# Extandboard.net
KiCad netlist of a schematic drawn in Altium Designer
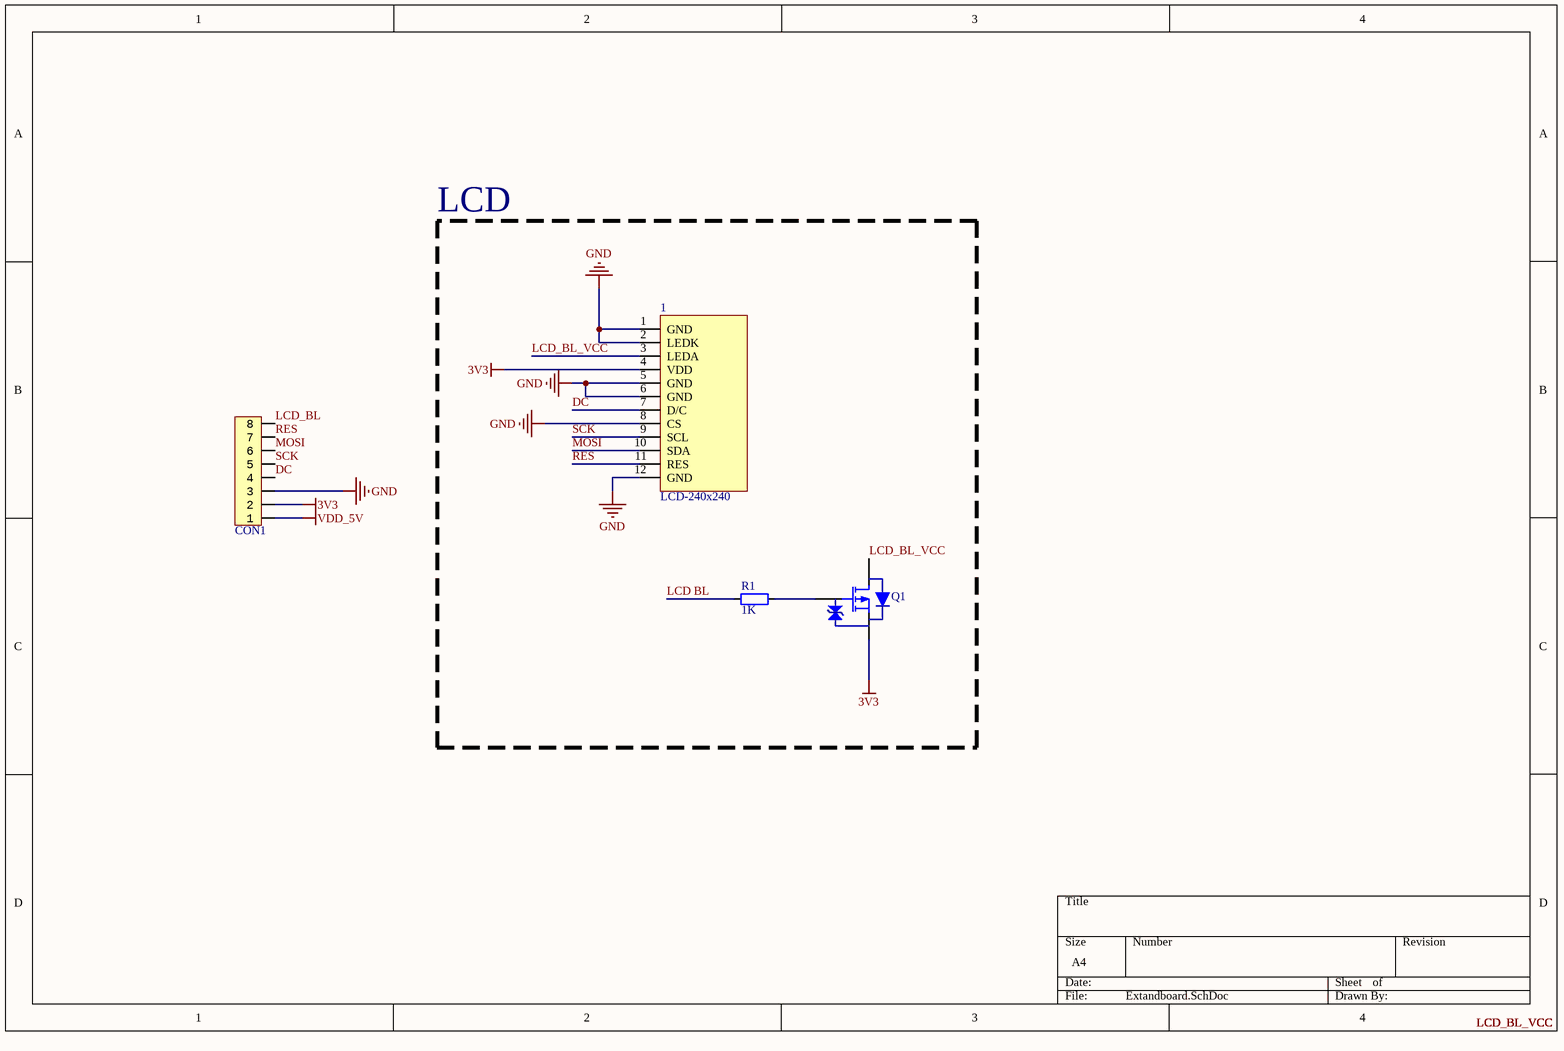
[diagram p0: Extandboard.SchDoc]

(export (version "E")
  (design (tool "Eeschema 10.0.6"))
  (components
    (comp (ref "1")
      (value "LCD-240x240")
      (footprint "LCD-240x240-NoHole")
      (description "显示屏")
      (libsource (lib "ExtendBoard") (part "LCD-240x240"))
    )
    (comp (ref "CON1")
      (value "FFC_0.5_8")
      (footprint "FFC_0.5_8")
      (description "FFC")
      (libsource (lib "ExtendBoard") (part "FFC_0.5_8"))
    )
    (comp (ref "Q1")
      (value "AO3415A")
      (footprint "SOT23-3")
      (description "MOSFET")
      (fields (field (name "PUBLISHER") "Altium Limited"))
      (libsource (lib "ExtendBoard") (part "AO3415A"))
    )
    (comp (ref "R1")
      (value "1K")
      (footprint "RES_0402")
      (description "Resistor")
      (libsource (lib "ExtendBoard") (part "电阻-0402"))
    )
  )
  (nets
    (net (code "1") (name "/DC") (class "Default")
      (node (ref "1") (pin "7") (pinfunction "D/C_7") (pintype "passive"))
      (node (ref "CON1") (pin "4") (pinfunction "4_4") (pintype "passive"))
    )
    (net (code "2") (name "/LCD BL") (class "Default")
      (node (ref "R1") (pin "1") (pinfunction "1_1") (pintype "passive"))
    )
    (net (code "3") (name "/LCD_BL") (class "Default")
      (node (ref "CON1") (pin "8") (pinfunction "8_8") (pintype "passive"))
    )
    (net (code "4") (name "/LCD_BL_VCC") (class "Default")
      (node (ref "1") (pin "3") (pinfunction "LEDA_3") (pintype "passive"))
      (node (ref "Q1") (pin "3") (pinfunction "D_3") (pintype "passive"))
    )
    (net (code "5") (name "/MOSI") (class "Default")
      (node (ref "1") (pin "10") (pinfunction "SDA_10") (pintype "passive"))
      (node (ref "CON1") (pin "6") (pinfunction "6_6") (pintype "passive"))
    )
    (net (code "6") (name "/RES") (class "Default")
      (node (ref "1") (pin "11") (pinfunction "RES_11") (pintype "passive"))
      (node (ref "CON1") (pin "7") (pinfunction "7_7") (pintype "passive"))
    )
    (net (code "7") (name "/SCK") (class "Default")
      (node (ref "1") (pin "9") (pinfunction "SCL_9") (pintype "passive"))
      (node (ref "CON1") (pin "5") (pinfunction "5_5") (pintype "passive"))
    )
    (net (code "8") (name "3V3") (class "Default")
      (node (ref "1") (pin "4") (pinfunction "VDD_4") (pintype "passive"))
      (node (ref "CON1") (pin "2") (pinfunction "2_2") (pintype "passive"))
      (node (ref "Q1") (pin "2") (pinfunction "S_2") (pintype "passive"))
    )
    (net (code "9") (name "GND") (class "Default")
      (node (ref "1") (pin "1") (pinfunction "GND_1") (pintype "passive"))
      (node (ref "1") (pin "12") (pinfunction "GND_12") (pintype "passive"))
      (node (ref "1") (pin "2") (pinfunction "LEDK_2") (pintype "passive"))
      (node (ref "1") (pin "5") (pinfunction "GND_5") (pintype "passive"))
      (node (ref "1") (pin "6") (pinfunction "GND_6") (pintype "passive"))
      (node (ref "1") (pin "8") (pinfunction "CS_8") (pintype "passive"))
      (node (ref "CON1") (pin "3") (pinfunction "3_3") (pintype "passive"))
    )
    (net (code "10") (name "Net-(Q1-G)") (class "Default")
      (node (ref "Q1") (pin "1") (pinfunction "G_1") (pintype "passive"))
      (node (ref "R1") (pin "2") (pinfunction "2_2") (pintype "passive"))
    )
    (net (code "11") (name "VDD_5V") (class "Default")
      (node (ref "CON1") (pin "1") (pinfunction "1_1") (pintype "passive"))
    )
  )
)
